# mram.net
KiCad netlist of a schematic drawn in Altium Designer
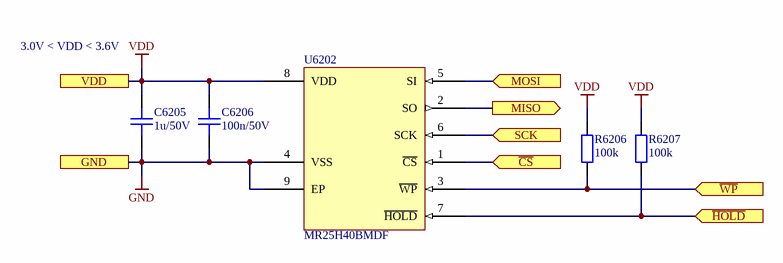
[diagram p0: mram.SchDoc]

(export (version "E")
  (design (tool "Eeschema 10.0.6"))
  (components
    (comp (ref "C6205")
      (value "1u/50V")
      (footprint "CAPC1608X08N")
      (description "MLCC")
      (fields (field (name "PART NUMBER") "gen_C_ceramic_1u_50V_X7R_0603") (field (name "TOLERANCE") "± 10%"))
      (libsource (lib "OE750") (part "C"))
    )
    (comp (ref "C6206")
      (value "100n/50V")
      (footprint "CAPC1005X06N")
      (description "MLCC")
      (fields (field (name "PART NUMBER") "gen_C_ceramic_100n_50V_X7R_0402"))
      (libsource (lib "OE750") (part "C"))
    )
    (comp (ref "R6206")
      (value "100k")
      (footprint "RESC1005X04N")
      (description "SMD Resistor 100k 0402")
      (fields (field (name "PART NUMBER") "gen_R_100k_0402") (field (name "TOLERANCE") "1%"))
      (libsource (lib "OE750") (part "R"))
    )
    (comp (ref "R6207")
      (value "100k")
      (footprint "RESC1005X04N")
      (description "SMD Resistor 100k 0402")
      (fields (field (name "PART NUMBER") "gen_R_100k_0402") (field (name "TOLERANCE") "1%"))
      (libsource (lib "OE750") (part "R"))
    )
    (comp (ref "U6202")
      (value "MR25H40BMDF")
      (footprint "MR25H40")
      (description "Magnetoresistive random access memory (MRAM) device")
      (fields (field (name "MANUFACTURER") "Everspin"))
      (libsource (lib "OE750") (part "MR25H40"))
    )
  )
  (nets
    (net (code "1") (name "/CS") (class "Default")
      (node (ref "U6202") (pin "1") (pinfunction "CS_1") (pintype "input"))
    )
    (net (code "2") (name "/HOLD") (class "Default")
      (node (ref "R6207") (pin "1") (pinfunction "1_1") (pintype "passive"))
      (node (ref "U6202") (pin "7") (pinfunction "HOLD_7") (pintype "input"))
    )
    (net (code "3") (name "/MISO") (class "Default")
      (node (ref "U6202") (pin "2") (pinfunction "SO_2") (pintype "output"))
    )
    (net (code "4") (name "/MOSI") (class "Default")
      (node (ref "U6202") (pin "5") (pinfunction "SI_5") (pintype "input"))
    )
    (net (code "5") (name "/SCK") (class "Default")
      (node (ref "U6202") (pin "6") (pinfunction "SCK_6") (pintype "input"))
    )
    (net (code "6") (name "/WP") (class "Default")
      (node (ref "R6206") (pin "1") (pinfunction "1_1") (pintype "passive"))
      (node (ref "U6202") (pin "3") (pinfunction "WP_3") (pintype "input"))
    )
    (net (code "7") (name "GND") (class "Default")
      (node (ref "C6205") (pin "1") (pinfunction "1_1") (pintype "passive"))
      (node (ref "C6206") (pin "1") (pinfunction "1_1") (pintype "passive"))
      (node (ref "U6202") (pin "4") (pinfunction "VSS_4") (pintype "power_in"))
      (node (ref "U6202") (pin "9") (pinfunction "EP_9") (pintype "power_in"))
    )
    (net (code "8") (name "VDD") (class "Default")
      (node (ref "C6205") (pin "2") (pinfunction "2_2") (pintype "passive"))
      (node (ref "C6206") (pin "2") (pinfunction "2_2") (pintype "passive"))
      (node (ref "R6206") (pin "2") (pinfunction "2_2") (pintype "passive"))
      (node (ref "R6207") (pin "2") (pinfunction "2_2") (pintype "passive"))
      (node (ref "U6202") (pin "8") (pinfunction "VDD_8") (pintype "power_in"))
    )
  )
)
